# powerboard1_1.net
KiCad netlist of a schematic drawn in EAGLE
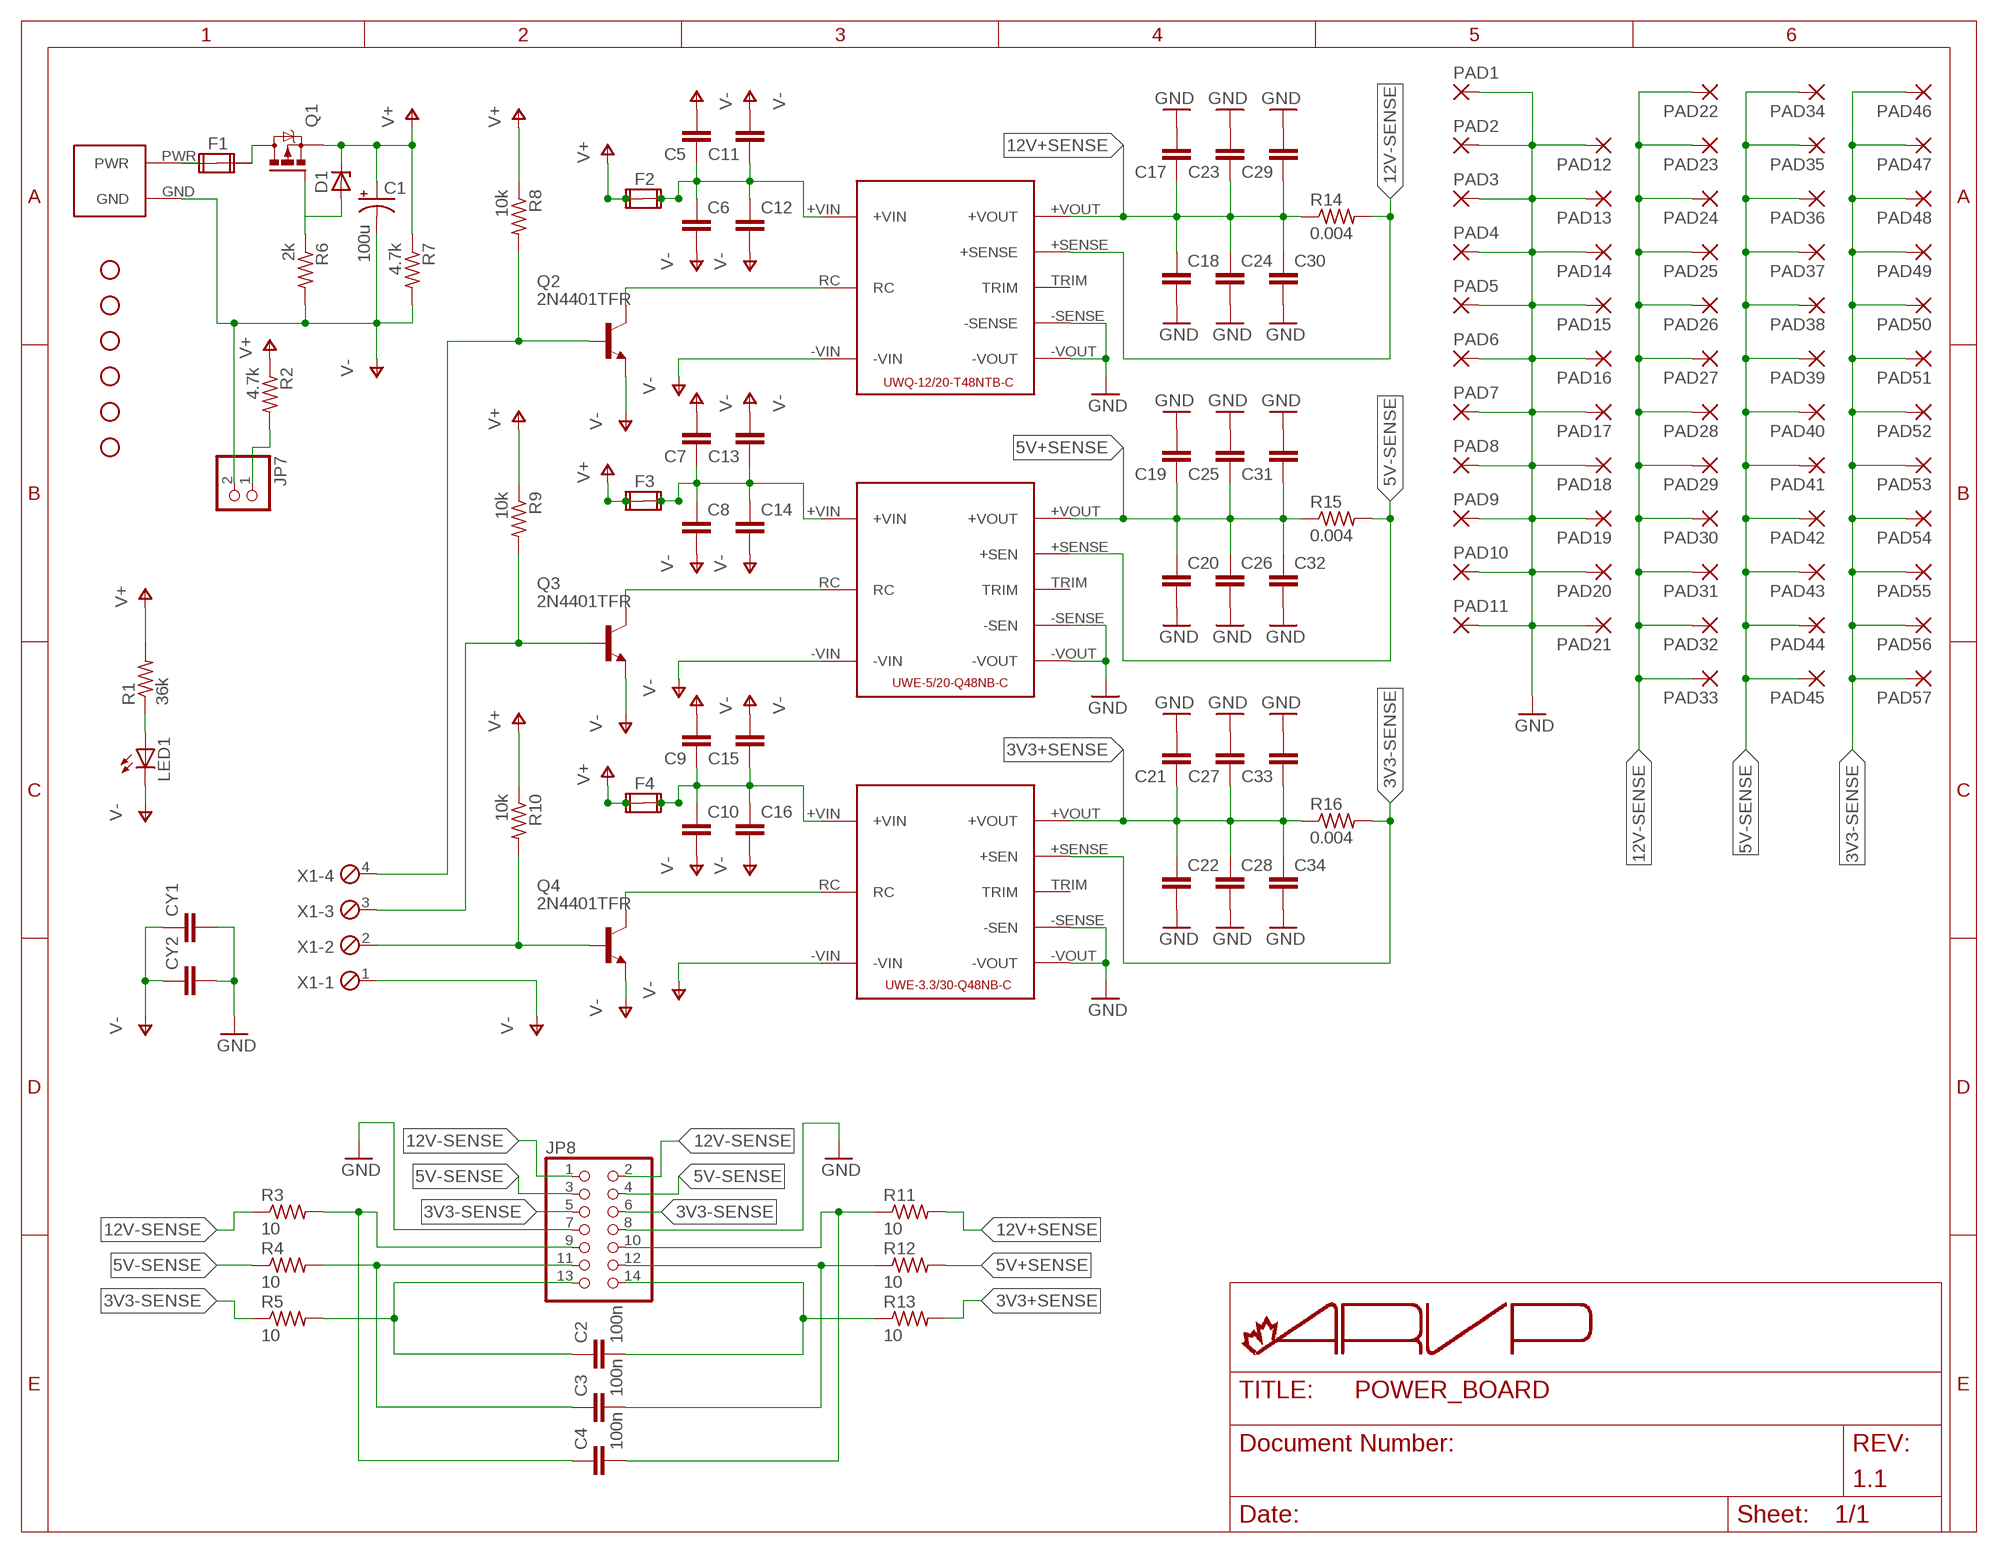
[diagram p0: schematic, sheet 1]

(export (version "E")
  (design (tool "Eeschema 10.0.6"))
  (components
    (comp (ref "C1")
      (value "100u")
      (footprint "eagle-import:E3,5-8")
      (libsource (lib "eagle-import") (part "CPOL-USE3.5-8"))
    )
    (comp (ref "C2")
      (value "100n")
      (footprint "eagle-import:C025-024X044")
      (libsource (lib "eagle-import") (part "C-EU025-024X044"))
    )
    (comp (ref "C3")
      (value "100n")
      (footprint "eagle-import:C025-024X044")
      (libsource (lib "eagle-import") (part "C-EU025-024X044"))
    )
    (comp (ref "C4")
      (value "100n")
      (footprint "eagle-import:C025-024X044")
      (libsource (lib "eagle-import") (part "C-EU025-024X044"))
    )
    (comp (ref "C5")
      (value "C-EU050-035X075")
      (footprint "eagle-import:C050-035X075")
      (libsource (lib "eagle-import") (part "C-EU050-035X075"))
    )
    (comp (ref "C6")
      (value "C-EU050-035X075")
      (footprint "eagle-import:C050-035X075")
      (libsource (lib "eagle-import") (part "C-EU050-035X075"))
    )
    (comp (ref "C7")
      (value "C-EU050-035X075")
      (footprint "eagle-import:C050-035X075")
      (libsource (lib "eagle-import") (part "C-EU050-035X075"))
    )
    (comp (ref "C8")
      (value "C-EU050-035X075")
      (footprint "eagle-import:C050-035X075")
      (libsource (lib "eagle-import") (part "C-EU050-035X075"))
    )
    (comp (ref "C9")
      (value "C-EU050-035X075")
      (footprint "eagle-import:C050-035X075")
      (libsource (lib "eagle-import") (part "C-EU050-035X075"))
    )
    (comp (ref "C10")
      (value "C-EU050-035X075")
      (footprint "eagle-import:C050-035X075")
      (libsource (lib "eagle-import") (part "C-EU050-035X075"))
    )
    (comp (ref "C11")
      (value "C-EU050-035X075")
      (footprint "eagle-import:C050-035X075")
      (libsource (lib "eagle-import") (part "C-EU050-035X075"))
    )
    (comp (ref "C12")
      (value "C-EU050-035X075")
      (footprint "eagle-import:C050-035X075")
      (libsource (lib "eagle-import") (part "C-EU050-035X075"))
    )
    (comp (ref "C13")
      (value "C-EU050-035X075")
      (footprint "eagle-import:C050-035X075")
      (libsource (lib "eagle-import") (part "C-EU050-035X075"))
    )
    (comp (ref "C14")
      (value "C-EU050-035X075")
      (footprint "eagle-import:C050-035X075")
      (libsource (lib "eagle-import") (part "C-EU050-035X075"))
    )
    (comp (ref "C15")
      (value "C-EU050-035X075")
      (footprint "eagle-import:C050-035X075")
      (libsource (lib "eagle-import") (part "C-EU050-035X075"))
    )
    (comp (ref "C16")
      (value "C-EU050-035X075")
      (footprint "eagle-import:C050-035X075")
      (libsource (lib "eagle-import") (part "C-EU050-035X075"))
    )
    (comp (ref "C17")
      (value "C-EU025-040X050")
      (footprint "eagle-import:C025-040X050")
      (libsource (lib "eagle-import") (part "C-EU025-040X050"))
    )
    (comp (ref "C18")
      (value "C-EU025-040X050")
      (footprint "eagle-import:C025-040X050")
      (libsource (lib "eagle-import") (part "C-EU025-040X050"))
    )
    (comp (ref "C19")
      (value "C-EU025-040X050")
      (footprint "eagle-import:C025-040X050")
      (libsource (lib "eagle-import") (part "C-EU025-040X050"))
    )
    (comp (ref "C20")
      (value "C-EU025-040X050")
      (footprint "eagle-import:C025-040X050")
      (libsource (lib "eagle-import") (part "C-EU025-040X050"))
    )
    (comp (ref "C21")
      (value "C-EU025-040X050")
      (footprint "eagle-import:C025-040X050")
      (libsource (lib "eagle-import") (part "C-EU025-040X050"))
    )
    (comp (ref "C22")
      (value "C-EU025-040X050")
      (footprint "eagle-import:C025-040X050")
      (libsource (lib "eagle-import") (part "C-EU025-040X050"))
    )
    (comp (ref "C23")
      (value "C-EU025-040X050")
      (footprint "eagle-import:C025-040X050")
      (libsource (lib "eagle-import") (part "C-EU025-040X050"))
    )
    (comp (ref "C24")
      (value "C-EU025-040X050")
      (footprint "eagle-import:C025-040X050")
      (libsource (lib "eagle-import") (part "C-EU025-040X050"))
    )
    (comp (ref "C25")
      (value "C-EU025-040X050")
      (footprint "eagle-import:C025-040X050")
      (libsource (lib "eagle-import") (part "C-EU025-040X050"))
    )
    (comp (ref "C26")
      (value "C-EU025-040X050")
      (footprint "eagle-import:C025-040X050")
      (libsource (lib "eagle-import") (part "C-EU025-040X050"))
    )
    (comp (ref "C27")
      (value "C-EU025-040X050")
      (footprint "eagle-import:C025-040X050")
      (libsource (lib "eagle-import") (part "C-EU025-040X050"))
    )
    (comp (ref "C28")
      (value "C-EU025-040X050")
      (footprint "eagle-import:C025-040X050")
      (libsource (lib "eagle-import") (part "C-EU025-040X050"))
    )
    (comp (ref "C29")
      (value "C-EU025-040X050")
      (footprint "eagle-import:C025-040X050")
      (libsource (lib "eagle-import") (part "C-EU025-040X050"))
    )
    (comp (ref "C30")
      (value "C-EU025-040X050")
      (footprint "eagle-import:C025-040X050")
      (libsource (lib "eagle-import") (part "C-EU025-040X050"))
    )
    (comp (ref "C31")
      (value "C-EU025-040X050")
      (footprint "eagle-import:C025-040X050")
      (libsource (lib "eagle-import") (part "C-EU025-040X050"))
    )
    (comp (ref "C32")
      (value "C-EU025-040X050")
      (footprint "eagle-import:C025-040X050")
      (libsource (lib "eagle-import") (part "C-EU025-040X050"))
    )
    (comp (ref "C33")
      (value "C-EU025-040X050")
      (footprint "eagle-import:C025-040X050")
      (libsource (lib "eagle-import") (part "C-EU025-040X050"))
    )
    (comp (ref "C34")
      (value "C-EU025-040X050")
      (footprint "eagle-import:C025-040X050")
      (libsource (lib "eagle-import") (part "C-EU025-040X050"))
    )
    (comp (ref "CY1")
      (value "CYYC7B5")
      (footprint "eagle-import:YC7B5")
      (libsource (lib "eagle-import") (part "CYYC7B5"))
    )
    (comp (ref "CY2")
      (value "CYYC7B5")
      (footprint "eagle-import:YC7B5")
      (libsource (lib "eagle-import") (part "CYYC7B5"))
    )
    (comp (ref "D1")
      (value "BZV10")
      (footprint "eagle-import:DO34Z7")
      (libsource (lib "eagle-import") (part "BZV10"))
    )
    (comp (ref "F1")
      (value "FUSE2P")
      (footprint "eagle-import:FUSE1")
      (libsource (lib "eagle-import") (part "FUSE2P"))
    )
    (comp (ref "F2")
      (value "FUSE2P")
      (footprint "eagle-import:FUSE1")
      (libsource (lib "eagle-import") (part "FUSE2P"))
    )
    (comp (ref "F3")
      (value "FUSE2P")
      (footprint "eagle-import:FUSE1")
      (libsource (lib "eagle-import") (part "FUSE2P"))
    )
    (comp (ref "F4")
      (value "FUSE2P")
      (footprint "eagle-import:FUSE1")
      (libsource (lib "eagle-import") (part "FUSE2P"))
    )
    (comp (ref "JP1")
      (value "STAND-OFF")
      (footprint "eagle-import:STAND-OFF")
      (libsource (lib "eagle-import") (part "STAND-OFF"))
    )
    (comp (ref "JP2")
      (value "STAND-OFF")
      (footprint "eagle-import:STAND-OFF")
      (libsource (lib "eagle-import") (part "STAND-OFF"))
    )
    (comp (ref "JP3")
      (value "STAND-OFF")
      (footprint "eagle-import:STAND-OFF")
      (libsource (lib "eagle-import") (part "STAND-OFF"))
    )
    (comp (ref "JP4")
      (value "STAND-OFF")
      (footprint "eagle-import:STAND-OFF")
      (libsource (lib "eagle-import") (part "STAND-OFF"))
    )
    (comp (ref "JP5")
      (value "STAND-OFF")
      (footprint "eagle-import:STAND-OFF")
      (libsource (lib "eagle-import") (part "STAND-OFF"))
    )
    (comp (ref "JP6")
      (value "STAND-OFF")
      (footprint "eagle-import:STAND-OFF")
      (libsource (lib "eagle-import") (part "STAND-OFF"))
    )
    (comp (ref "JP7")
      (value "PINHD-1X2")
      (footprint "eagle-import:1X02")
      (libsource (lib "eagle-import") (part "PINHD-1X2"))
    )
    (comp (ref "JP8")
      (value "PINHD-2X7")
      (footprint "eagle-import:2X07")
      (libsource (lib "eagle-import") (part "PINHD-2X7"))
    )
    (comp (ref "LED1")
      (value "LED3MM")
      (footprint "eagle-import:LED3MM")
      (libsource (lib "eagle-import") (part "LED3MM"))
    )
    (comp (ref "P$1")
      (value "AND_PWR")
      (footprint "eagle-import:AND_PWR")
      (libsource (lib "eagle-import") (part "AND_PWR"))
    )
    (comp (ref "PAD1")
      (value "WIREPAD3,17/1,3")
      (footprint "eagle-import:3,17_1,3")
      (libsource (lib "eagle-import") (part "WIREPAD3,17/1,3"))
    )
    (comp (ref "PAD2")
      (value "WIREPAD3,17/1,3")
      (footprint "eagle-import:3,17_1,3")
      (libsource (lib "eagle-import") (part "WIREPAD3,17/1,3"))
    )
    (comp (ref "PAD3")
      (value "WIREPAD3,17/1,3")
      (footprint "eagle-import:3,17_1,3")
      (libsource (lib "eagle-import") (part "WIREPAD3,17/1,3"))
    )
    (comp (ref "PAD4")
      (value "WIREPAD3,17/1,3")
      (footprint "eagle-import:3,17_1,3")
      (libsource (lib "eagle-import") (part "WIREPAD3,17/1,3"))
    )
    (comp (ref "PAD5")
      (value "WIREPAD3,17/1,3")
      (footprint "eagle-import:3,17_1,3")
      (libsource (lib "eagle-import") (part "WIREPAD3,17/1,3"))
    )
    (comp (ref "PAD6")
      (value "WIREPAD3,17/1,3")
      (footprint "eagle-import:3,17_1,3")
      (libsource (lib "eagle-import") (part "WIREPAD3,17/1,3"))
    )
    (comp (ref "PAD7")
      (value "WIREPAD3,17/1,3")
      (footprint "eagle-import:3,17_1,3")
      (libsource (lib "eagle-import") (part "WIREPAD3,17/1,3"))
    )
    (comp (ref "PAD8")
      (value "WIREPAD3,17/1,3")
      (footprint "eagle-import:3,17_1,3")
      (libsource (lib "eagle-import") (part "WIREPAD3,17/1,3"))
    )
    (comp (ref "PAD9")
      (value "WIREPAD3,17/1,3")
      (footprint "eagle-import:3,17_1,3")
      (libsource (lib "eagle-import") (part "WIREPAD3,17/1,3"))
    )
    (comp (ref "PAD10")
      (value "WIREPAD3,17/1,3")
      (footprint "eagle-import:3,17_1,3")
      (libsource (lib "eagle-import") (part "WIREPAD3,17/1,3"))
    )
    (comp (ref "PAD11")
      (value "WIREPAD3,17/1,3")
      (footprint "eagle-import:3,17_1,3")
      (libsource (lib "eagle-import") (part "WIREPAD3,17/1,3"))
    )
    (comp (ref "PAD12")
      (value "WIREPAD3,17/1,3")
      (footprint "eagle-import:3,17_1,3")
      (libsource (lib "eagle-import") (part "WIREPAD3,17/1,3"))
    )
    (comp (ref "PAD13")
      (value "WIREPAD3,17/1,3")
      (footprint "eagle-import:3,17_1,3")
      (libsource (lib "eagle-import") (part "WIREPAD3,17/1,3"))
    )
    (comp (ref "PAD14")
      (value "WIREPAD3,17/1,3")
      (footprint "eagle-import:3,17_1,3")
      (libsource (lib "eagle-import") (part "WIREPAD3,17/1,3"))
    )
    (comp (ref "PAD15")
      (value "WIREPAD3,17/1,3")
      (footprint "eagle-import:3,17_1,3")
      (libsource (lib "eagle-import") (part "WIREPAD3,17/1,3"))
    )
    (comp (ref "PAD16")
      (value "WIREPAD3,17/1,3")
      (footprint "eagle-import:3,17_1,3")
      (libsource (lib "eagle-import") (part "WIREPAD3,17/1,3"))
    )
    (comp (ref "PAD17")
      (value "WIREPAD3,17/1,3")
      (footprint "eagle-import:3,17_1,3")
      (libsource (lib "eagle-import") (part "WIREPAD3,17/1,3"))
    )
    (comp (ref "PAD18")
      (value "WIREPAD3,17/1,3")
      (footprint "eagle-import:3,17_1,3")
      (libsource (lib "eagle-import") (part "WIREPAD3,17/1,3"))
    )
    (comp (ref "PAD19")
      (value "WIREPAD3,17/1,3")
      (footprint "eagle-import:3,17_1,3")
      (libsource (lib "eagle-import") (part "WIREPAD3,17/1,3"))
    )
    (comp (ref "PAD20")
      (value "WIREPAD3,17/1,3")
      (footprint "eagle-import:3,17_1,3")
      (libsource (lib "eagle-import") (part "WIREPAD3,17/1,3"))
    )
    (comp (ref "PAD21")
      (value "WIREPAD3,17/1,3")
      (footprint "eagle-import:3,17_1,3")
      (libsource (lib "eagle-import") (part "WIREPAD3,17/1,3"))
    )
    (comp (ref "PAD22")
      (value "WIREPAD3,17/1,3")
      (footprint "eagle-import:3,17_1,3")
      (libsource (lib "eagle-import") (part "WIREPAD3,17/1,3"))
    )
    (comp (ref "PAD23")
      (value "WIREPAD3,17/1,3")
      (footprint "eagle-import:3,17_1,3")
      (libsource (lib "eagle-import") (part "WIREPAD3,17/1,3"))
    )
    (comp (ref "PAD24")
      (value "WIREPAD3,17/1,3")
      (footprint "eagle-import:3,17_1,3")
      (libsource (lib "eagle-import") (part "WIREPAD3,17/1,3"))
    )
    (comp (ref "PAD25")
      (value "WIREPAD3,17/1,3")
      (footprint "eagle-import:3,17_1,3")
      (libsource (lib "eagle-import") (part "WIREPAD3,17/1,3"))
    )
    (comp (ref "PAD26")
      (value "WIREPAD3,17/1,3")
      (footprint "eagle-import:3,17_1,3")
      (libsource (lib "eagle-import") (part "WIREPAD3,17/1,3"))
    )
    (comp (ref "PAD27")
      (value "WIREPAD3,17/1,3")
      (footprint "eagle-import:3,17_1,3")
      (libsource (lib "eagle-import") (part "WIREPAD3,17/1,3"))
    )
    (comp (ref "PAD28")
      (value "WIREPAD3,17/1,3")
      (footprint "eagle-import:3,17_1,3")
      (libsource (lib "eagle-import") (part "WIREPAD3,17/1,3"))
    )
    (comp (ref "PAD29")
      (value "WIREPAD3,17/1,3")
      (footprint "eagle-import:3,17_1,3")
      (libsource (lib "eagle-import") (part "WIREPAD3,17/1,3"))
    )
    (comp (ref "PAD30")
      (value "WIREPAD3,17/1,3")
      (footprint "eagle-import:3,17_1,3")
      (libsource (lib "eagle-import") (part "WIREPAD3,17/1,3"))
    )
    (comp (ref "PAD31")
      (value "WIREPAD3,17/1,3")
      (footprint "eagle-import:3,17_1,3")
      (libsource (lib "eagle-import") (part "WIREPAD3,17/1,3"))
    )
    (comp (ref "PAD32")
      (value "WIREPAD3,17/1,3")
      (footprint "eagle-import:3,17_1,3")
      (libsource (lib "eagle-import") (part "WIREPAD3,17/1,3"))
    )
    (comp (ref "PAD33")
      (value "WIREPAD3,17/1,3")
      (footprint "eagle-import:3,17_1,3")
      (libsource (lib "eagle-import") (part "WIREPAD3,17/1,3"))
    )
    (comp (ref "PAD34")
      (value "WIREPAD3,17/1,3")
      (footprint "eagle-import:3,17_1,3")
      (libsource (lib "eagle-import") (part "WIREPAD3,17/1,3"))
    )
    (comp (ref "PAD35")
      (value "WIREPAD3,17/1,3")
      (footprint "eagle-import:3,17_1,3")
      (libsource (lib "eagle-import") (part "WIREPAD3,17/1,3"))
    )
    (comp (ref "PAD36")
      (value "WIREPAD3,17/1,3")
      (footprint "eagle-import:3,17_1,3")
      (libsource (lib "eagle-import") (part "WIREPAD3,17/1,3"))
    )
    (comp (ref "PAD37")
      (value "WIREPAD3,17/1,3")
      (footprint "eagle-import:3,17_1,3")
      (libsource (lib "eagle-import") (part "WIREPAD3,17/1,3"))
    )
    (comp (ref "PAD38")
      (value "WIREPAD3,17/1,3")
      (footprint "eagle-import:3,17_1,3")
      (libsource (lib "eagle-import") (part "WIREPAD3,17/1,3"))
    )
    (comp (ref "PAD39")
      (value "WIREPAD3,17/1,3")
      (footprint "eagle-import:3,17_1,3")
      (libsource (lib "eagle-import") (part "WIREPAD3,17/1,3"))
    )
    (comp (ref "PAD40")
      (value "WIREPAD3,17/1,3")
      (footprint "eagle-import:3,17_1,3")
      (libsource (lib "eagle-import") (part "WIREPAD3,17/1,3"))
    )
    (comp (ref "PAD41")
      (value "WIREPAD3,17/1,3")
      (footprint "eagle-import:3,17_1,3")
      (libsource (lib "eagle-import") (part "WIREPAD3,17/1,3"))
    )
    (comp (ref "PAD42")
      (value "WIREPAD3,17/1,3")
      (footprint "eagle-import:3,17_1,3")
      (libsource (lib "eagle-import") (part "WIREPAD3,17/1,3"))
    )
    (comp (ref "PAD43")
      (value "WIREPAD3,17/1,3")
      (footprint "eagle-import:3,17_1,3")
      (libsource (lib "eagle-import") (part "WIREPAD3,17/1,3"))
    )
    (comp (ref "PAD44")
      (value "WIREPAD3,17/1,3")
      (footprint "eagle-import:3,17_1,3")
      (libsource (lib "eagle-import") (part "WIREPAD3,17/1,3"))
    )
    (comp (ref "PAD45")
      (value "WIREPAD3,17/1,3")
      (footprint "eagle-import:3,17_1,3")
      (libsource (lib "eagle-import") (part "WIREPAD3,17/1,3"))
    )
    (comp (ref "PAD46")
      (value "WIREPAD3,17/1,3")
      (footprint "eagle-import:3,17_1,3")
      (libsource (lib "eagle-import") (part "WIREPAD3,17/1,3"))
    )
    (comp (ref "PAD47")
      (value "WIREPAD3,17/1,3")
      (footprint "eagle-import:3,17_1,3")
      (libsource (lib "eagle-import") (part "WIREPAD3,17/1,3"))
    )
    (comp (ref "PAD48")
      (value "WIREPAD3,17/1,3")
      (footprint "eagle-import:3,17_1,3")
      (libsource (lib "eagle-import") (part "WIREPAD3,17/1,3"))
    )
    (comp (ref "PAD49")
      (value "WIREPAD3,17/1,3")
      (footprint "eagle-import:3,17_1,3")
      (libsource (lib "eagle-import") (part "WIREPAD3,17/1,3"))
    )
    (comp (ref "PAD50")
      (value "WIREPAD3,17/1,3")
      (footprint "eagle-import:3,17_1,3")
      (libsource (lib "eagle-import") (part "WIREPAD3,17/1,3"))
    )
    (comp (ref "PAD51")
      (value "WIREPAD3,17/1,3")
      (footprint "eagle-import:3,17_1,3")
      (libsource (lib "eagle-import") (part "WIREPAD3,17/1,3"))
    )
    (comp (ref "PAD52")
      (value "WIREPAD3,17/1,3")
      (footprint "eagle-import:3,17_1,3")
      (libsource (lib "eagle-import") (part "WIREPAD3,17/1,3"))
    )
    (comp (ref "PAD53")
      (value "WIREPAD3,17/1,3")
      (footprint "eagle-import:3,17_1,3")
      (libsource (lib "eagle-import") (part "WIREPAD3,17/1,3"))
    )
    (comp (ref "PAD54")
      (value "WIREPAD3,17/1,3")
      (footprint "eagle-import:3,17_1,3")
      (libsource (lib "eagle-import") (part "WIREPAD3,17/1,3"))
    )
    (comp (ref "PAD55")
      (value "WIREPAD3,17/1,3")
      (footprint "eagle-import:3,17_1,3")
      (libsource (lib "eagle-import") (part "WIREPAD3,17/1,3"))
    )
    (comp (ref "PAD56")
      (value "WIREPAD3,17/1,3")
      (footprint "eagle-import:3,17_1,3")
      (libsource (lib "eagle-import") (part "WIREPAD3,17/1,3"))
    )
    (comp (ref "PAD57")
      (value "WIREPAD3,17/1,3")
      (footprint "eagle-import:3,17_1,3")
      (libsource (lib "eagle-import") (part "WIREPAD3,17/1,3"))
    )
    (comp (ref "Q1")
      (value "IPP80P03P4L04AKSA1")
      (footprint "eagle-import:TO220BV")
      (libsource (lib "eagle-import") (part "IPP80P03P4L04AKSA1"))
    )
    (comp (ref "Q2")
      (value "2N4401TFR")
      (footprint "eagle-import:TO92-EBC")
      (libsource (lib "eagle-import") (part "2N4401TFR"))
    )
    (comp (ref "Q3")
      (value "2N4401TFR")
      (footprint "eagle-import:TO92-EBC")
      (libsource (lib "eagle-import") (part "2N4401TFR"))
    )
    (comp (ref "Q4")
      (value "2N4401TFR")
      (footprint "eagle-import:TO92-EBC")
      (libsource (lib "eagle-import") (part "2N4401TFR"))
    )
    (comp (ref "R1")
      (value "36k")
      (footprint "eagle-import:0204_7")
      (libsource (lib "eagle-import") (part "resistor_R-US_0204/7"))
    )
    (comp (ref "R2")
      (value "4.7k")
      (footprint "eagle-import:0204_7")
      (libsource (lib "eagle-import") (part "resistor_R-US_0204/7"))
    )
    (comp (ref "R3")
      (value "10")
      (footprint "eagle-import:0204_5")
      (libsource (lib "eagle-import") (part "R-US_0204/5"))
    )
    (comp (ref "R4")
      (value "10")
      (footprint "eagle-import:0204_5")
      (libsource (lib "eagle-import") (part "R-US_0204/5"))
    )
    (comp (ref "R5")
      (value "10")
      (footprint "eagle-import:0204_5")
      (libsource (lib "eagle-import") (part "R-US_0204/5"))
    )
    (comp (ref "R6")
      (value "2k")
      (footprint "eagle-import:0204_7")
      (libsource (lib "eagle-import") (part "resistor_R-US_0204/7"))
    )
    (comp (ref "R7")
      (value "4.7k")
      (footprint "eagle-import:0204_7")
      (libsource (lib "eagle-import") (part "resistor_R-US_0204/7"))
    )
    (comp (ref "R8")
      (value "10k")
      (footprint "eagle-import:0204_7")
      (libsource (lib "eagle-import") (part "resistor_R-US_0204/7"))
    )
    (comp (ref "R9")
      (value "10k")
      (footprint "eagle-import:0204_7")
      (libsource (lib "eagle-import") (part "resistor_R-US_0204/7"))
    )
    (comp (ref "R10")
      (value "10k")
      (footprint "eagle-import:0204_7")
      (libsource (lib "eagle-import") (part "resistor_R-US_0204/7"))
    )
    (comp (ref "R11")
      (value "10")
      (footprint "eagle-import:0204_5")
      (libsource (lib "eagle-import") (part "R-US_0204/5"))
    )
    (comp (ref "R12")
      (value "10")
      (footprint "eagle-import:0204_5")
      (libsource (lib "eagle-import") (part "R-US_0204/5"))
    )
    (comp (ref "R13")
      (value "10")
      (footprint "eagle-import:0204_5")
      (libsource (lib "eagle-import") (part "R-US_0204/5"))
    )
    (comp (ref "R14")
      (value "0.004")
      (footprint "eagle-import:0617_22")
      (libsource (lib "eagle-import") (part "R-US_0617/22"))
    )
    (comp (ref "R15")
      (value "0.004")
      (footprint "eagle-import:0617_22")
      (libsource (lib "eagle-import") (part "R-US_0617/22"))
    )
    (comp (ref "R16")
      (value "0.004")
      (footprint "eagle-import:0617_22")
      (libsource (lib "eagle-import") (part "R-US_0617/22"))
    )
    (comp (ref "U1")
      (value "UWQ-12/20-T48NTB-C")
      (footprint "eagle-import:UWQ-12_20-T48")
      (libsource (lib "eagle-import") (part "UWQ-12/20-T48NTB-C"))
    )
    (comp (ref "U2")
      (value "UWE-5/20-Q48NB-C")
      (footprint "eagle-import:UWE-100-120W")
      (libsource (lib "eagle-import") (part "UWE-5/20-Q48NB-C"))
    )
    (comp (ref "U3")
      (value "UWE-3.3/30-Q48NB-C")
      (footprint "eagle-import:UWE-100-120W")
      (libsource (lib "eagle-import") (part "UWE-3.3/30-Q48NB-C"))
    )
    (comp (ref "X1")
      (value "MPT4")
      (footprint "eagle-import:4POL254")
      (libsource (lib "eagle-import") (part "MPT4"))
    )
  )
  (nets
    (net (code "1") (name "3V3+SENSE") (class "Default")
      (node (ref "C21") (pin "1") (pinfunction "1_1") (pintype "passive"))
      (node (ref "C22") (pin "1") (pinfunction "1_1") (pintype "passive"))
      (node (ref "C27") (pin "1") (pinfunction "1_1") (pintype "passive"))
      (node (ref "C28") (pin "1") (pinfunction "1_1") (pintype "passive"))
      (node (ref "C33") (pin "1") (pinfunction "1_1") (pintype "passive"))
      (node (ref "C34") (pin "1") (pinfunction "1_1") (pintype "passive"))
      (node (ref "R13") (pin "2") (pinfunction "2_2") (pintype "passive"))
      (node (ref "R16") (pin "1") (pinfunction "1_1") (pintype "passive"))
      (node (ref "U3") (pin "+VOUT") (pinfunction "+VOUT_+VOUT") (pintype "power_in"))
    )
    (net (code "2") (name "3V3-SENSE") (class "Default")
      (node (ref "JP8") (pin "5") (pinfunction "5_5") (pintype "passive"))
      (node (ref "JP8") (pin "6") (pinfunction "6_6") (pintype "passive"))
      (node (ref "PAD46") (pin "1") (pinfunction "P_1") (pintype "passive"))
      (node (ref "PAD47") (pin "1") (pinfunction "P_1") (pintype "passive"))
      (node (ref "PAD48") (pin "1") (pinfunction "P_1") (pintype "passive"))
      (node (ref "PAD49") (pin "1") (pinfunction "P_1") (pintype "passive"))
      (node (ref "PAD50") (pin "1") (pinfunction "P_1") (pintype "passive"))
      (node (ref "PAD51") (pin "1") (pinfunction "P_1") (pintype "passive"))
      (node (ref "PAD52") (pin "1") (pinfunction "P_1") (pintype "passive"))
      (node (ref "PAD53") (pin "1") (pinfunction "P_1") (pintype "passive"))
      (node (ref "PAD54") (pin "1") (pinfunction "P_1") (pintype "passive"))
      (node (ref "PAD55") (pin "1") (pinfunction "P_1") (pintype "passive"))
      (node (ref "PAD56") (pin "1") (pinfunction "P_1") (pintype "passive"))
      (node (ref "PAD57") (pin "1") (pinfunction "P_1") (pintype "passive"))
      (node (ref "R16") (pin "2") (pinfunction "2_2") (pintype "passive"))
      (node (ref "R5") (pin "1") (pinfunction "1_1") (pintype "passive"))
      (node (ref "U3") (pin "+SENSE") (pinfunction "+SEN_+SENSE") (pintype "bidirectional"))
    )
    (net (code "3") (name "5V+SENSE") (class "Default")
      (node (ref "C19") (pin "1") (pinfunction "1_1") (pintype "passive"))
      (node (ref "C20") (pin "1") (pinfunction "1_1") (pintype "passive"))
      (node (ref "C25") (pin "1") (pinfunction "1_1") (pintype "passive"))
      (node (ref "C26") (pin "1") (pinfunction "1_1") (pintype "passive"))
      (node (ref "C31") (pin "1") (pinfunction "1_1") (pintype "passive"))
      (node (ref "C32") (pin "1") (pinfunction "1_1") (pintype "passive"))
      (node (ref "R12") (pin "2") (pinfunction "2_2") (pintype "passive"))
      (node (ref "R15") (pin "1") (pinfunction "1_1") (pintype "passive"))
      (node (ref "U2") (pin "+VOUT") (pinfunction "+VOUT_+VOUT") (pintype "power_in"))
    )
    (net (code "4") (name "5V-SENSE") (class "Default")
      (node (ref "JP8") (pin "3") (pinfunction "3_3") (pintype "passive"))
      (node (ref "JP8") (pin "4") (pinfunction "4_4") (pintype "passive"))
      (node (ref "PAD34") (pin "1") (pinfunction "P_1") (pintype "passive"))
      (node (ref "PAD35") (pin "1") (pinfunction "P_1") (pintype "passive"))
      (node (ref "PAD36") (pin "1") (pinfunction "P_1") (pintype "passive"))
      (node (ref "PAD37") (pin "1") (pinfunction "P_1") (pintype "passive"))
      (node (ref "PAD38") (pin "1") (pinfunction "P_1") (pintype "passive"))
      (node (ref "PAD39") (pin "1") (pinfunction "P_1") (pintype "passive"))
      (node (ref "PAD40") (pin "1") (pinfunction "P_1") (pintype "passive"))
      (node (ref "PAD41") (pin "1") (pinfunction "P_1") (pintype "passive"))
      (node (ref "PAD42") (pin "1") (pinfunction "P_1") (pintype "passive"))
      (node (ref "PAD43") (pin "1") (pinfunction "P_1") (pintype "passive"))
      (node (ref "PAD44") (pin "1") (pinfunction "P_1") (pintype "passive"))
      (node (ref "PAD45") (pin "1") (pinfunction "P_1") (pintype "passive"))
      (node (ref "R15") (pin "2") (pinfunction "2_2") (pintype "passive"))
      (node (ref "R4") (pin "1") (pinfunction "1_1") (pintype "passive"))
      (node (ref "U2") (pin "+SENSE") (pinfunction "+SEN_+SENSE") (pintype "bidirectional"))
    )
    (net (code "5") (name "12V+SENSE") (class "Default")
      (node (ref "C17") (pin "1") (pinfunction "1_1") (pintype "passive"))
      (node (ref "C18") (pin "1") (pinfunction "1_1") (pintype "passive"))
      (node (ref "C23") (pin "1") (pinfunction "1_1") (pintype "passive"))
      (node (ref "C24") (pin "1") (pinfunction "1_1") (pintype "passive"))
      (node (ref "C29") (pin "1") (pinfunction "1_1") (pintype "passive"))
      (node (ref "C30") (pin "1") (pinfunction "1_1") (pintype "passive"))
      (node (ref "R11") (pin "2") (pinfunction "2_2") (pintype "passive"))
      (node (ref "R14") (pin "1") (pinfunction "1_1") (pintype "passive"))
      (node (ref "U1") (pin "+VOUT") (pinfunction "+VOUT_+VOUT") (pintype "power_in"))
    )
    (net (code "6") (name "12V-SENSE") (class "Default")
      (node (ref "JP8") (pin "1") (pinfunction "1_1") (pintype "passive"))
      (node (ref "JP8") (pin "2") (pinfunction "2_2") (pintype "passive"))
      (node (ref "PAD22") (pin "1") (pinfunction "P_1") (pintype "passive"))
      (node (ref "PAD23") (pin "1") (pinfunction "P_1") (pintype "passive"))
      (node (ref "PAD24") (pin "1") (pinfunction "P_1") (pintype "passive"))
      (node (ref "PAD25") (pin "1") (pinfunction "P_1") (pintype "passive"))
      (node (ref "PAD26") (pin "1") (pinfunction "P_1") (pintype "passive"))
      (node (ref "PAD27") (pin "1") (pinfunction "P_1") (pintype "passive"))
      (node (ref "PAD28") (pin "1") (pinfunction "P_1") (pintype "passive"))
      (node (ref "PAD29") (pin "1") (pinfunction "P_1") (pintype "passive"))
      (node (ref "PAD30") (pin "1") (pinfunction "P_1") (pintype "passive"))
      (node (ref "PAD31") (pin "1") (pinfunction "P_1") (pintype "passive"))
      (node (ref "PAD32") (pin "1") (pinfunction "P_1") (pintype "passive"))
      (node (ref "PAD33") (pin "1") (pinfunction "P_1") (pintype "passive"))
      (node (ref "R14") (pin "2") (pinfunction "2_2") (pintype "passive"))
      (node (ref "R3") (pin "1") (pinfunction "1_1") (pintype "passive"))
      (node (ref "U1") (pin "+SENSE") (pinfunction "+SENSE_+SENSE") (pintype "bidirectional"))
    )
    (net (code "7") (name "GND") (class "Default")
      (node (ref "C17") (pin "2") (pinfunction "2_2") (pintype "passive"))
      (node (ref "C18") (pin "2") (pinfunction "2_2") (pintype "passive"))
      (node (ref "C19") (pin "2") (pinfunction "2_2") (pintype "passive"))
      (node (ref "C20") (pin "2") (pinfunction "2_2") (pintype "passive"))
      (node (ref "C21") (pin "2") (pinfunction "2_2") (pintype "passive"))
      (node (ref "C22") (pin "2") (pinfunction "2_2") (pintype "passive"))
      (node (ref "C23") (pin "2") (pinfunction "2_2") (pintype "passive"))
      (node (ref "C24") (pin "2") (pinfunction "2_2") (pintype "passive"))
      (node (ref "C25") (pin "2") (pinfunction "2_2") (pintype "passive"))
      (node (ref "C26") (pin "2") (pinfunction "2_2") (pintype "passive"))
      (node (ref "C27") (pin "2") (pinfunction "2_2") (pintype "passive"))
      (node (ref "C28") (pin "2") (pinfunction "2_2") (pintype "passive"))
      (node (ref "C29") (pin "2") (pinfunction "2_2") (pintype "passive"))
      (node (ref "C30") (pin "2") (pinfunction "2_2") (pintype "passive"))
      (node (ref "C31") (pin "2") (pinfunction "2_2") (pintype "passive"))
      (node (ref "C32") (pin "2") (pinfunction "2_2") (pintype "passive"))
      (node (ref "C33") (pin "2") (pinfunction "2_2") (pintype "passive"))
      (node (ref "C34") (pin "2") (pinfunction "2_2") (pintype "passive"))
      (node (ref "CY1") (pin "2") (pinfunction "2_2") (pintype "passive"))
      (node (ref "CY2") (pin "2") (pinfunction "2_2") (pintype "passive"))
      (node (ref "JP8") (pin "7") (pinfunction "7_7") (pintype "passive"))
      (node (ref "JP8") (pin "8") (pinfunction "8_8") (pintype "passive"))
      (node (ref "PAD1") (pin "1") (pinfunction "P_1") (pintype "passive"))
      (node (ref "PAD10") (pin "1") (pinfunction "P_1") (pintype "passive"))
      (node (ref "PAD11") (pin "1") (pinfunction "P_1") (pintype "passive"))
      (node (ref "PAD12") (pin "1") (pinfunction "P_1") (pintype "passive"))
      (node (ref "PAD13") (pin "1") (pinfunction "P_1") (pintype "passive"))
      (node (ref "PAD14") (pin "1") (pinfunction "P_1") (pintype "passive"))
      (node (ref "PAD15") (pin "1") (pinfunction "P_1") (pintype "passive"))
      (node (ref "PAD16") (pin "1") (pinfunction "P_1") (pintype "passive"))
      (node (ref "PAD17") (pin "1") (pinfunction "P_1") (pintype "passive"))
      (node (ref "PAD18") (pin "1") (pinfunction "P_1") (pintype "passive"))
      (node (ref "PAD19") (pin "1") (pinfunction "P_1") (pintype "passive"))
      (node (ref "PAD2") (pin "1") (pinfunction "P_1") (pintype "passive"))
      (node (ref "PAD20") (pin "1") (pinfunction "P_1") (pintype "passive"))
      (node (ref "PAD21") (pin "1") (pinfunction "P_1") (pintype "passive"))
      (node (ref "PAD3") (pin "1") (pinfunction "P_1") (pintype "passive"))
      (node (ref "PAD4") (pin "1") (pinfunction "P_1") (pintype "passive"))
      (node (ref "PAD5") (pin "1") (pinfunction "P_1") (pintype "passive"))
      (node (ref "PAD6") (pin "1") (pinfunction "P_1") (pintype "passive"))
      (node (ref "PAD7") (pin "1") (pinfunction "P_1") (pintype "passive"))
      (node (ref "PAD8") (pin "1") (pinfunction "P_1") (pintype "passive"))
      (node (ref "PAD9") (pin "1") (pinfunction "P_1") (pintype "passive"))
      (node (ref "U1") (pin "-SENSE") (pinfunction "-SENSE_-SENSE") (pintype "bidirectional"))
      (node (ref "U1") (pin "-VOUT") (pinfunction "-VOUT_-VOUT") (pintype "power_in"))
      (node (ref "U2") (pin "-SENSE") (pinfunction "-SEN_-SENSE") (pintype "bidirectional"))
      (node (ref "U2") (pin "-VOUT") (pinfunction "-VOUT_-VOUT") (pintype "power_in"))
      (node (ref "U3") (pin "-SENSE") (pinfunction "-SEN_-SENSE") (pintype "bidirectional"))
      (node (ref "U3") (pin "-VOUT") (pinfunction "-VOUT_-VOUT") (pintype "power_in"))
    )
    (net (code "8") (name "Net-(C2-Pad1)") (class "Default")
      (node (ref "C2") (pin "1") (pinfunction "1_1") (pintype "passive"))
      (node (ref "JP8") (pin "13") (pinfunction "13_13") (pintype "passive"))
      (node (ref "R5") (pin "2") (pinfunction "2_2") (pintype "passive"))
    )
    (net (code "9") (name "Net-(C2-Pad2)") (class "Default")
      (node (ref "C2") (pin "2") (pinfunction "2_2") (pintype "passive"))
      (node (ref "JP8") (pin "14") (pinfunction "14_14") (pintype "passive"))
      (node (ref "R13") (pin "1") (pinfunction "1_1") (pintype "passive"))
    )
    (net (code "10") (name "Net-(C3-Pad1)") (class "Default")
      (node (ref "C3") (pin "1") (pinfunction "1_1") (pintype "passive"))
      (node (ref "JP8") (pin "11") (pinfunction "11_11") (pintype "passive"))
      (node (ref "R4") (pin "2") (pinfunction "2_2") (pintype "passive"))
    )
    (net (code "11") (name "Net-(C3-Pad2)") (class "Default")
      (node (ref "C3") (pin "2") (pinfunction "2_2") (pintype "passive"))
      (node (ref "JP8") (pin "12") (pinfunction "12_12") (pintype "passive"))
      (node (ref "R12") (pin "1") (pinfunction "1_1") (pintype "passive"))
    )
    (net (code "12") (name "Net-(C4-Pad1)") (class "Default")
      (node (ref "C4") (pin "1") (pinfunction "1_1") (pintype "passive"))
      (node (ref "JP8") (pin "9") (pinfunction "9_9") (pintype "passive"))
      (node (ref "R3") (pin "2") (pinfunction "2_2") (pintype "passive"))
    )
    (net (code "13") (name "Net-(C4-Pad2)") (class "Default")
      (node (ref "C4") (pin "2") (pinfunction "2_2") (pintype "passive"))
      (node (ref "JP8") (pin "10") (pinfunction "10_10") (pintype "passive"))
      (node (ref "R11") (pin "1") (pinfunction "1_1") (pintype "passive"))
    )
    (net (code "14") (name "Net-(C10-Pad1)") (class "Default")
      (node (ref "C10") (pin "1") (pinfunction "1_1") (pintype "passive"))
      (node (ref "C15") (pin "1") (pinfunction "1_1") (pintype "passive"))
      (node (ref "C16") (pin "1") (pinfunction "1_1") (pintype "passive"))
      (node (ref "C9") (pin "1") (pinfunction "1_1") (pintype "passive"))
      (node (ref "F4") (pin "2A") (pinfunction "2A_2A") (pintype "passive"))
      (node (ref "F4") (pin "2B") (pinfunction "2B_2B") (pintype "passive"))
      (node (ref "U3") (pin "+VIN") (pinfunction "+VIN_+VIN") (pintype "power_in"))
    )
    (net (code "15") (name "Net-(C11-Pad1)") (class "Default")
      (node (ref "C11") (pin "1") (pinfunction "1_1") (pintype "passive"))
      (node (ref "C12") (pin "1") (pinfunction "1_1") (pintype "passive"))
      (node (ref "C5") (pin "1") (pinfunction "1_1") (pintype "passive"))
      (node (ref "C6") (pin "1") (pinfunction "1_1") (pintype "passive"))
      (node (ref "F2") (pin "2A") (pinfunction "2A_2A") (pintype "passive"))
      (node (ref "F2") (pin "2B") (pinfunction "2B_2B") (pintype "passive"))
      (node (ref "U1") (pin "+VIN") (pinfunction "+VIN_+VIN") (pintype "power_in"))
    )
    (net (code "16") (name "Net-(C13-Pad1)") (class "Default")
      (node (ref "C13") (pin "1") (pinfunction "1_1") (pintype "passive"))
      (node (ref "C14") (pin "1") (pinfunction "1_1") (pintype "passive"))
      (node (ref "C7") (pin "1") (pinfunction "1_1") (pintype "passive"))
      (node (ref "C8") (pin "1") (pinfunction "1_1") (pintype "passive"))
      (node (ref "F3") (pin "2A") (pinfunction "2A_2A") (pintype "passive"))
      (node (ref "F3") (pin "2B") (pinfunction "2B_2B") (pintype "passive"))
      (node (ref "U2") (pin "+VIN") (pinfunction "+VIN_+VIN") (pintype "power_in"))
    )
    (net (code "17") (name "Net-(D1-PadA)") (class "Default")
      (node (ref "D1") (pin "A") (pinfunction "A_A") (pintype "passive"))
      (node (ref "Q1") (pin "G") (pinfunction "G_G") (pintype "power_in"))
      (node (ref "R6") (pin "1") (pinfunction "1_1") (pintype "passive"))
    )
    (net (code "18") (name "Net-(F1-Pad1A)") (class "Default")
      (node (ref "F1") (pin "1A") (pinfunction "1A_1A") (pintype "passive"))
      (node (ref "F1") (pin "1B") (pinfunction "1B_1B") (pintype "passive"))
      (node (ref "P$1") (pin "PWR") (pinfunction "PWR_PWR") (pintype "bidirectional"))
    )
    (net (code "19") (name "Net-(F1-Pad2A)") (class "Default")
      (node (ref "F1") (pin "2A") (pinfunction "2A_2A") (pintype "passive"))
      (node (ref "F1") (pin "2B") (pinfunction "2B_2B") (pintype "passive"))
      (node (ref "Q1") (pin "D") (pinfunction "D_D") (pintype "power_in"))
    )
    (net (code "20") (name "Net-(JP7-Pad1)") (class "Default")
      (node (ref "JP7") (pin "1") (pinfunction "1_1") (pintype "passive"))
      (node (ref "R2") (pin "2") (pinfunction "2_2") (pintype "passive"))
    )
    (net (code "21") (name "Net-(LED1-PadA)") (class "Default")
      (node (ref "LED1") (pin "A") (pinfunction "A_A") (pintype "passive"))
      (node (ref "R1") (pin "1") (pinfunction "1_1") (pintype "passive"))
    )
    (net (code "22") (name "Net-(Q2-PadC)") (class "Default")
      (node (ref "Q2") (pin "C") (pinfunction "C_C") (pintype "passive"))
      (node (ref "U1") (pin "RC") (pinfunction "RC_RC") (pintype "bidirectional"))
    )
    (net (code "23") (name "Net-(Q3-PadC)") (class "Default")
      (node (ref "Q3") (pin "C") (pinfunction "C_C") (pintype "passive"))
      (node (ref "U2") (pin "RC") (pinfunction "RC_RC") (pintype "bidirectional"))
    )
    (net (code "24") (name "Net-(Q4-PadC)") (class "Default")
      (node (ref "Q4") (pin "C") (pinfunction "C_C") (pintype "passive"))
      (node (ref "U3") (pin "RC") (pinfunction "RC_RC") (pintype "bidirectional"))
    )
    (net (code "25") (name "Net-(X1B-1)") (class "Default")
      (node (ref "Q4") (pin "B") (pinfunction "B_B") (pintype "passive"))
      (node (ref "R10") (pin "2") (pinfunction "2_2") (pintype "passive"))
      (node (ref "X1") (pin "2") (pinfunction "1_2") (pintype "passive"))
    )
    (net (code "26") (name "Net-(X1C-1)") (class "Default")
      (node (ref "Q3") (pin "B") (pinfunction "B_B") (pintype "passive"))
      (node (ref "R9") (pin "2") (pinfunction "2_2") (pintype "passive"))
      (node (ref "X1") (pin "3") (pinfunction "1_3") (pintype "passive"))
    )
    (net (code "27") (name "Net-(X1D-1)") (class "Default")
      (node (ref "Q2") (pin "B") (pinfunction "B_B") (pintype "passive"))
      (node (ref "R8") (pin "2") (pinfunction "2_2") (pintype "passive"))
      (node (ref "X1") (pin "4") (pinfunction "1_4") (pintype "passive"))
    )
    (net (code "28") (name "V+") (class "Default")
      (node (ref "C1") (pin "+") (pinfunction "+_+") (pintype "passive"))
      (node (ref "D1") (pin "C") (pinfunction "C_C") (pintype "passive"))
      (node (ref "F2") (pin "1A") (pinfunction "1A_1A") (pintype "passive"))
      (node (ref "F2") (pin "1B") (pinfunction "1B_1B") (pintype "passive"))
      (node (ref "F3") (pin "1A") (pinfunction "1A_1A") (pintype "passive"))
      (node (ref "F3") (pin "1B") (pinfunction "1B_1B") (pintype "passive"))
      (node (ref "F4") (pin "1A") (pinfunction "1A_1A") (pintype "passive"))
      (node (ref "F4") (pin "1B") (pinfunction "1B_1B") (pintype "passive"))
      (node (ref "Q1") (pin "S") (pinfunction "S_S") (pintype "power_in"))
      (node (ref "R1") (pin "2") (pinfunction "2_2") (pintype "passive"))
      (node (ref "R10") (pin "1") (pinfunction "1_1") (pintype "passive"))
      (node (ref "R2") (pin "1") (pinfunction "1_1") (pintype "passive"))
      (node (ref "R7") (pin "1") (pinfunction "1_1") (pintype "passive"))
      (node (ref "R8") (pin "1") (pinfunction "1_1") (pintype "passive"))
      (node (ref "R9") (pin "1") (pinfunction "1_1") (pintype "passive"))
    )
    (net (code "29") (name "V-") (class "Default")
      (node (ref "C1") (pin "-") (pinfunction "-_-") (pintype "passive"))
      (node (ref "C10") (pin "2") (pinfunction "2_2") (pintype "passive"))
      (node (ref "C11") (pin "2") (pinfunction "2_2") (pintype "passive"))
      (node (ref "C12") (pin "2") (pinfunction "2_2") (pintype "passive"))
      (node (ref "C13") (pin "2") (pinfunction "2_2") (pintype "passive"))
      (node (ref "C14") (pin "2") (pinfunction "2_2") (pintype "passive"))
      (node (ref "C15") (pin "2") (pinfunction "2_2") (pintype "passive"))
      (node (ref "C16") (pin "2") (pinfunction "2_2") (pintype "passive"))
      (node (ref "C5") (pin "2") (pinfunction "2_2") (pintype "passive"))
      (node (ref "C6") (pin "2") (pinfunction "2_2") (pintype "passive"))
      (node (ref "C7") (pin "2") (pinfunction "2_2") (pintype "passive"))
      (node (ref "C8") (pin "2") (pinfunction "2_2") (pintype "passive"))
      (node (ref "C9") (pin "2") (pinfunction "2_2") (pintype "passive"))
      (node (ref "CY1") (pin "1") (pinfunction "1_1") (pintype "passive"))
      (node (ref "CY2") (pin "1") (pinfunction "1_1") (pintype "passive"))
      (node (ref "JP7") (pin "2") (pinfunction "2_2") (pintype "passive"))
      (node (ref "LED1") (pin "K") (pinfunction "C_K") (pintype "passive"))
      (node (ref "P$1") (pin "GND") (pinfunction "GND_GND") (pintype "bidirectional"))
      (node (ref "Q2") (pin "E") (pinfunction "E_E") (pintype "passive"))
      (node (ref "Q3") (pin "E") (pinfunction "E_E") (pintype "passive"))
      (node (ref "Q4") (pin "E") (pinfunction "E_E") (pintype "passive"))
      (node (ref "R6") (pin "2") (pinfunction "2_2") (pintype "passive"))
      (node (ref "R7") (pin "2") (pinfunction "2_2") (pintype "passive"))
      (node (ref "U1") (pin "-VIN") (pinfunction "-VIN_-VIN") (pintype "power_in"))
      (node (ref "U2") (pin "-VIN") (pinfunction "-VIN_-VIN") (pintype "power_in"))
      (node (ref "U3") (pin "-VIN") (pinfunction "-VIN_-VIN") (pintype "power_in"))
      (node (ref "X1") (pin "1") (pinfunction "1_1") (pintype "passive"))
    )
    (net (code "30") (name "unconnected-(U1-PadTRIM)") (class "Default")
      (node (ref "U1") (pin "TRIM") (pinfunction "TRIM_TRIM") (pintype "bidirectional"))
    )
    (net (code "31") (name "unconnected-(U2-PadTRIM)") (class "Default")
      (node (ref "U2") (pin "TRIM") (pinfunction "TRIM_TRIM") (pintype "bidirectional"))
    )
    (net (code "32") (name "unconnected-(U3-PadTRIM)") (class "Default")
      (node (ref "U3") (pin "TRIM") (pinfunction "TRIM_TRIM") (pintype "bidirectional"))
    )
  )
)
